# SchematicAmplifier.net
KiCad netlist of a schematic drawn in EAGLE
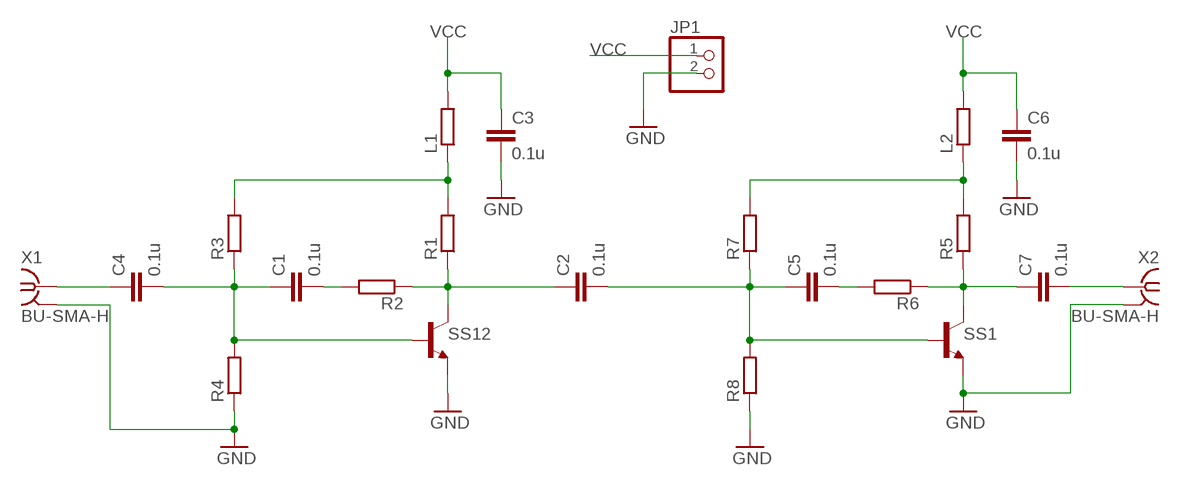
[diagram p0: schematic, sheet 1]

(export (version "E")
  (design (tool "Eeschema 10.0.6"))
  (components
    (comp (ref "C1")
      (value "0.1u")
      (footprint "eagle-import:C0805")
      (libsource (lib "eagle-import") (part "C-EUC0805"))
    )
    (comp (ref "C2")
      (value "0.1u")
      (footprint "eagle-import:C0805")
      (libsource (lib "eagle-import") (part "C-EUC0805"))
    )
    (comp (ref "C3")
      (value "0.1u")
      (footprint "eagle-import:C0805")
      (libsource (lib "eagle-import") (part "C-EUC0805"))
    )
    (comp (ref "C4")
      (value "0.1u")
      (footprint "eagle-import:C0805")
      (libsource (lib "eagle-import") (part "C-EUC0805"))
    )
    (comp (ref "C5")
      (value "0.1u")
      (footprint "eagle-import:C0805")
      (libsource (lib "eagle-import") (part "C-EUC0805"))
    )
    (comp (ref "C6")
      (value "0.1u")
      (footprint "eagle-import:C0805")
      (libsource (lib "eagle-import") (part "C-EUC0805"))
    )
    (comp (ref "C7")
      (value "0.1u")
      (footprint "eagle-import:C0805")
      (libsource (lib "eagle-import") (part "C-EUC0805"))
    )
    (comp (ref "JP1")
      (value "PINHD-1X2")
      (footprint "eagle-import:1X02")
      (libsource (lib "eagle-import") (part "PINHD-1X2"))
    )
    (comp (ref "L1")
      (value "R-EU_M0805")
      (footprint "eagle-import:M0805")
      (libsource (lib "eagle-import") (part "resistor_R-EU_M0805"))
    )
    (comp (ref "L2")
      (value "R-EU_M0805")
      (footprint "eagle-import:M0805")
      (libsource (lib "eagle-import") (part "resistor_R-EU_M0805"))
    )
    (comp (ref "R1")
      (value "R-EU_R1206")
      (footprint "eagle-import:R1206")
      (libsource (lib "eagle-import") (part "R-EU_R1206"))
    )
    (comp (ref "R2")
      (value "R-EU_R1206")
      (footprint "eagle-import:R1206")
      (libsource (lib "eagle-import") (part "R-EU_R1206"))
    )
    (comp (ref "R3")
      (value "R-EU_R1206")
      (footprint "eagle-import:R1206")
      (libsource (lib "eagle-import") (part "R-EU_R1206"))
    )
    (comp (ref "R4")
      (value "R-EU_R1206")
      (footprint "eagle-import:R1206")
      (libsource (lib "eagle-import") (part "R-EU_R1206"))
    )
    (comp (ref "R5")
      (value "R-EU_R1206")
      (footprint "eagle-import:R1206")
      (libsource (lib "eagle-import") (part "R-EU_R1206"))
    )
    (comp (ref "R6")
      (value "R-EU_R1206")
      (footprint "eagle-import:R1206")
      (libsource (lib "eagle-import") (part "R-EU_R1206"))
    )
    (comp (ref "R7")
      (value "R-EU_R1206")
      (footprint "eagle-import:R1206")
      (libsource (lib "eagle-import") (part "R-EU_R1206"))
    )
    (comp (ref "R8")
      (value "R-EU_R1206")
      (footprint "eagle-import:R1206")
      (libsource (lib "eagle-import") (part "R-EU_R1206"))
    )
    (comp (ref "SS1")
      (value "-NPN-TO92")
      (footprint "eagle-import:TO92")
      (libsource (lib "eagle-import") (part "-NPN-TO92"))
    )
    (comp (ref "SS12")
      (value "-NPN-TO92")
      (footprint "eagle-import:TO92")
      (libsource (lib "eagle-import") (part "-NPN-TO92"))
    )
    (comp (ref "X1")
      (value "BU-SMA-H")
      (footprint "eagle-import:BU-SMA-H")
      (libsource (lib "eagle-import") (part "BU-SMA-H"))
    )
    (comp (ref "X2")
      (value "BU-SMA-H")
      (footprint "eagle-import:BU-SMA-H")
      (libsource (lib "eagle-import") (part "BU-SMA-H"))
    )
  )
  (nets
    (net (code "1") (name "/VCC") (class "Default")
      (node (ref "C3") (pin "1") (pinfunction "1_1") (pintype "passive"))
      (node (ref "C6") (pin "1") (pinfunction "1_1") (pintype "passive"))
      (node (ref "JP1") (pin "1") (pinfunction "1_1") (pintype "passive"))
      (node (ref "L1") (pin "2") (pinfunction "2_2") (pintype "passive"))
      (node (ref "L2") (pin "2") (pinfunction "2_2") (pintype "passive"))
    )
    (net (code "2") (name "GND") (class "Default")
      (node (ref "C3") (pin "2") (pinfunction "2_2") (pintype "passive"))
      (node (ref "C6") (pin "2") (pinfunction "2_2") (pintype "passive"))
      (node (ref "JP1") (pin "2") (pinfunction "2_2") (pintype "passive"))
      (node (ref "R4") (pin "1") (pinfunction "1_1") (pintype "passive"))
      (node (ref "R8") (pin "1") (pinfunction "1_1") (pintype "passive"))
      (node (ref "SS1") (pin "1") (pinfunction "E_1") (pintype "passive"))
      (node (ref "SS12") (pin "1") (pinfunction "E_1") (pintype "passive"))
      (node (ref "X1") (pin "2") (pinfunction "2_2") (pintype "passive"))
      (node (ref "X1") (pin "3") (pinfunction "2_3") (pintype "passive"))
      (node (ref "X1") (pin "4") (pinfunction "2_4") (pintype "passive"))
      (node (ref "X1") (pin "5") (pinfunction "2_5") (pintype "passive"))
      (node (ref "X2") (pin "2") (pinfunction "2_2") (pintype "passive"))
      (node (ref "X2") (pin "3") (pinfunction "2_3") (pintype "passive"))
      (node (ref "X2") (pin "4") (pinfunction "2_4") (pintype "passive"))
      (node (ref "X2") (pin "5") (pinfunction "2_5") (pintype "passive"))
    )
    (net (code "3") (name "Net-(C1-Pad2)") (class "Default")
      (node (ref "C1") (pin "2") (pinfunction "2_2") (pintype "passive"))
      (node (ref "R2") (pin "2") (pinfunction "2_2") (pintype "passive"))
    )
    (net (code "4") (name "Net-(C4-Pad1)") (class "Default")
      (node (ref "C4") (pin "1") (pinfunction "1_1") (pintype "passive"))
      (node (ref "X1") (pin "1") (pinfunction "1_1") (pintype "passive"))
    )
    (net (code "5") (name "Net-(C5-Pad2)") (class "Default")
      (node (ref "C5") (pin "2") (pinfunction "2_2") (pintype "passive"))
      (node (ref "R6") (pin "2") (pinfunction "2_2") (pintype "passive"))
    )
    (net (code "6") (name "Net-(C7-Pad2)") (class "Default")
      (node (ref "C7") (pin "2") (pinfunction "2_2") (pintype "passive"))
      (node (ref "X2") (pin "1") (pinfunction "1_1") (pintype "passive"))
    )
    (net (code "7") (name "Net-(L1-Pad1)") (class "Default")
      (node (ref "L1") (pin "1") (pinfunction "1_1") (pintype "passive"))
      (node (ref "R1") (pin "2") (pinfunction "2_2") (pintype "passive"))
      (node (ref "R3") (pin "2") (pinfunction "2_2") (pintype "passive"))
    )
    (net (code "8") (name "Net-(L2-Pad1)") (class "Default")
      (node (ref "L2") (pin "1") (pinfunction "1_1") (pintype "passive"))
      (node (ref "R5") (pin "2") (pinfunction "2_2") (pintype "passive"))
      (node (ref "R7") (pin "2") (pinfunction "2_2") (pintype "passive"))
    )
    (net (code "9") (name "Net-(SS1-B)") (class "Default")
      (node (ref "C2") (pin "2") (pinfunction "2_2") (pintype "passive"))
      (node (ref "C5") (pin "1") (pinfunction "1_1") (pintype "passive"))
      (node (ref "R7") (pin "1") (pinfunction "1_1") (pintype "passive"))
      (node (ref "R8") (pin "2") (pinfunction "2_2") (pintype "passive"))
      (node (ref "SS1") (pin "2") (pinfunction "B_2") (pintype "passive"))
    )
    (net (code "10") (name "Net-(SS1-C)") (class "Default")
      (node (ref "C7") (pin "1") (pinfunction "1_1") (pintype "passive"))
      (node (ref "R5") (pin "1") (pinfunction "1_1") (pintype "passive"))
      (node (ref "R6") (pin "1") (pinfunction "1_1") (pintype "passive"))
      (node (ref "SS1") (pin "3") (pinfunction "C_3") (pintype "passive"))
    )
    (net (code "11") (name "Net-(SS12-B)") (class "Default")
      (node (ref "C1") (pin "1") (pinfunction "1_1") (pintype "passive"))
      (node (ref "C4") (pin "2") (pinfunction "2_2") (pintype "passive"))
      (node (ref "R3") (pin "1") (pinfunction "1_1") (pintype "passive"))
      (node (ref "R4") (pin "2") (pinfunction "2_2") (pintype "passive"))
      (node (ref "SS12") (pin "2") (pinfunction "B_2") (pintype "passive"))
    )
    (net (code "12") (name "Net-(SS12-C)") (class "Default")
      (node (ref "C2") (pin "1") (pinfunction "1_1") (pintype "passive"))
      (node (ref "R1") (pin "1") (pinfunction "1_1") (pintype "passive"))
      (node (ref "R2") (pin "1") (pinfunction "1_1") (pintype "passive"))
      (node (ref "SS12") (pin "3") (pinfunction "C_3") (pintype "passive"))
    )
  )
)
